# ScreenBoard.net
KiCad netlist of a schematic drawn in Altium Designer
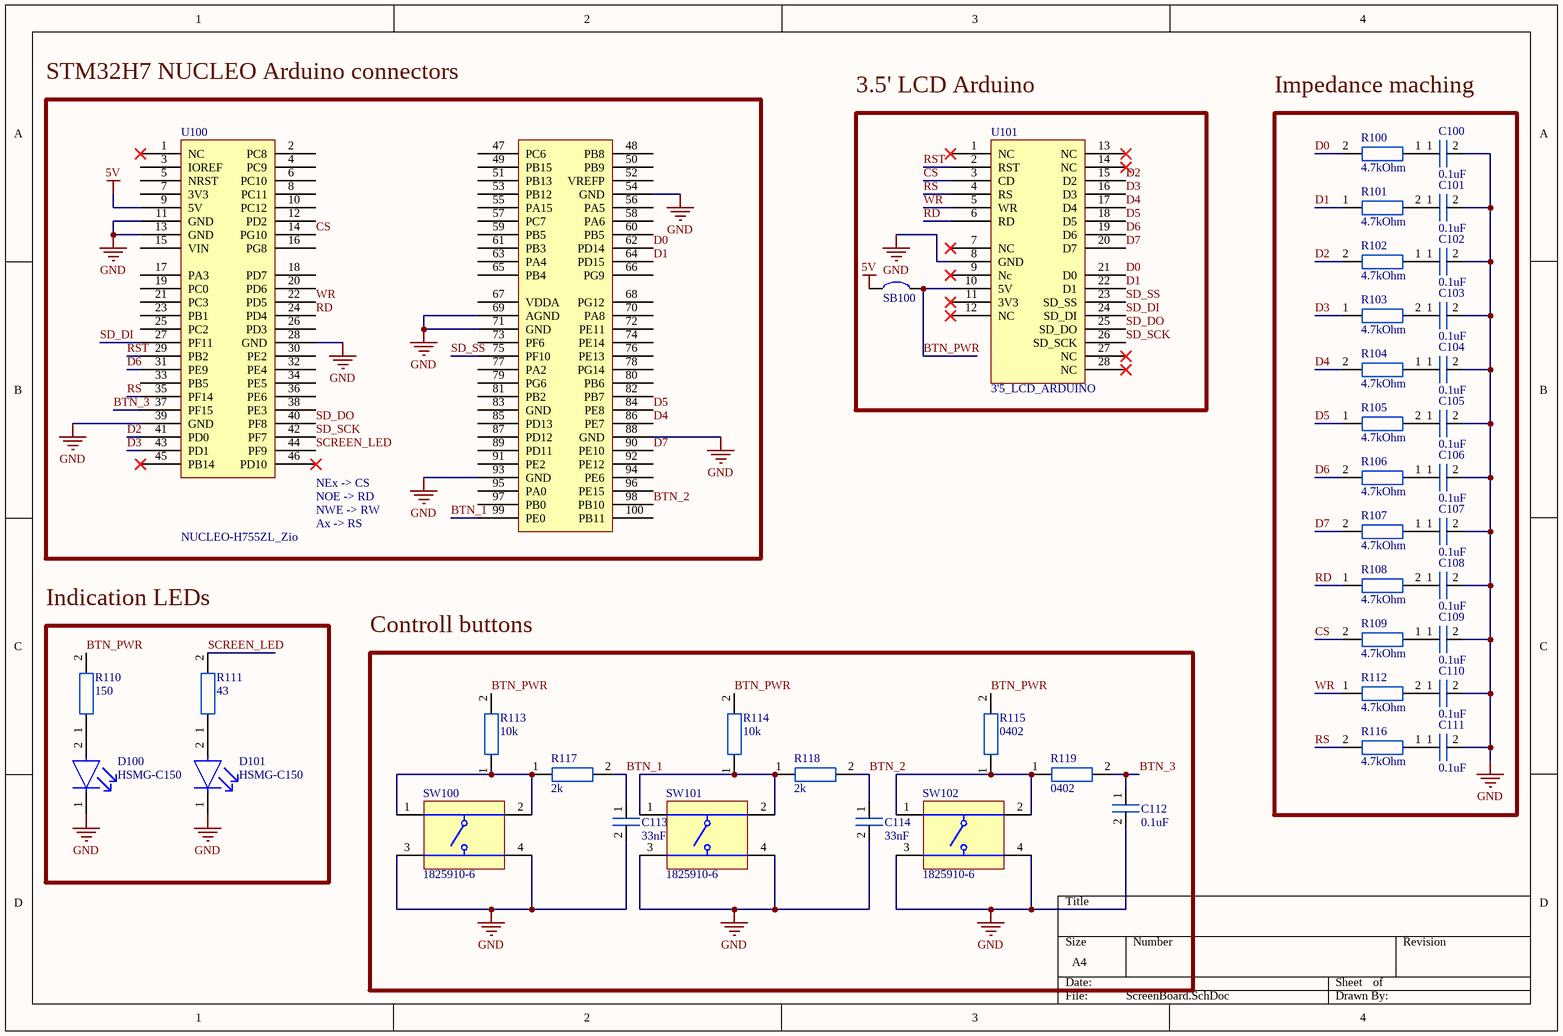
[diagram p0: ScreenBoard.SchDoc]

(export (version "E")
  (design (tool "Eeschema 10.0.6"))
  (components
    (comp (ref "C100")
      (value "0.1uF")
      (footprint "0402_footprint")
      (description "0402 capacitor")
      (libsource (lib "Schlib1") (part "Capacitor_0402"))
    )
    (comp (ref "C101")
      (value "0.1uF")
      (footprint "0402_footprint")
      (description "0402 capacitor")
      (libsource (lib "Schlib1") (part "Capacitor_0402"))
    )
    (comp (ref "C102")
      (value "0.1uF")
      (footprint "0402_footprint")
      (description "0402 capacitor")
      (libsource (lib "Schlib1") (part "Capacitor_0402"))
    )
    (comp (ref "C103")
      (value "0.1uF")
      (footprint "0402_footprint")
      (description "0402 capacitor")
      (libsource (lib "Schlib1") (part "Capacitor_0402"))
    )
    (comp (ref "C104")
      (value "0.1uF")
      (footprint "0402_footprint")
      (description "0402 capacitor")
      (libsource (lib "Schlib1") (part "Capacitor_0402"))
    )
    (comp (ref "C105")
      (value "0.1uF")
      (footprint "0402_footprint")
      (description "0402 capacitor")
      (libsource (lib "Schlib1") (part "Capacitor_0402"))
    )
    (comp (ref "C106")
      (value "0.1uF")
      (footprint "0402_footprint")
      (description "0402 capacitor")
      (libsource (lib "Schlib1") (part "Capacitor_0402"))
    )
    (comp (ref "C107")
      (value "0.1uF")
      (footprint "0402_footprint")
      (description "0402 capacitor")
      (libsource (lib "Schlib1") (part "Capacitor_0402"))
    )
    (comp (ref "C108")
      (value "0.1uF")
      (footprint "0402_footprint")
      (description "0402 capacitor")
      (libsource (lib "Schlib1") (part "Capacitor_0402"))
    )
    (comp (ref "C109")
      (value "0.1uF")
      (footprint "0402_footprint")
      (description "0402 capacitor")
      (libsource (lib "Schlib1") (part "Capacitor_0402"))
    )
    (comp (ref "C110")
      (value "0.1uF")
      (footprint "0402_footprint")
      (description "0402 capacitor")
      (libsource (lib "Schlib1") (part "Capacitor_0402"))
    )
    (comp (ref "C111")
      (value "0.1uF")
      (footprint "0402_footprint")
      (description "0402 capacitor")
      (libsource (lib "Schlib1") (part "Capacitor_0402"))
    )
    (comp (ref "C112")
      (value "0.1uF")
      (footprint "0402_footprint")
      (description "0402 capacitor")
      (libsource (lib "Schlib1") (part "Capacitor_0402"))
    )
    (comp (ref "C113")
      (value "33nF")
      (footprint "0402_footprint")
      (description "0402 capacitor")
      (libsource (lib "Schlib1") (part "Capacitor_0402"))
    )
    (comp (ref "C114")
      (value "33nF")
      (footprint "0402_footprint")
      (description "0402 capacitor")
      (libsource (lib "Schlib1") (part "Capacitor_0402"))
    )
    (comp (ref "D100")
      (value "HSMG-C150")
      (footprint "FP-HSMG-C150-MFG")
      (description "LED GREEN DIFFUSED 1206 SMD")
      (fields
        (field (name "MANUFACTURER") "Broadcom")
        (field (name "OCTOPART") "https://octopart.com/hsmg-c150-broadcom-71131304")
      )
      (libsource (lib "Altium Content Vault") (part "8706943c75ba83719d021d2fdc84c58"))
    )
    (comp (ref "D101")
      (value "HSMG-C150")
      (footprint "FP-HSMG-C150-MFG")
      (description "LED GREEN DIFFUSED 1206 SMD")
      (fields
        (field (name "MANUFACTURER") "Broadcom")
        (field (name "OCTOPART") "https://octopart.com/hsmg-c150-broadcom-71131304")
      )
      (libsource (lib "Altium Content Vault") (part "8706943c75ba83719d021d2fdc84c58"))
    )
    (comp (ref "R100")
      (value "4.7kOhm")
      (footprint "0402_footprint")
      (description "0402 resistor")
      (libsource (lib "Schlib1") (part "Resistor_0402"))
    )
    (comp (ref "R101")
      (value "4.7kOhm")
      (footprint "0402_footprint")
      (description "0402 resistor")
      (libsource (lib "Schlib1") (part "Resistor_0402"))
    )
    (comp (ref "R102")
      (value "4.7kOhm")
      (footprint "0402_footprint")
      (description "0402 resistor")
      (libsource (lib "Schlib1") (part "Resistor_0402"))
    )
    (comp (ref "R103")
      (value "4.7kOhm")
      (footprint "0402_footprint")
      (description "0402 resistor")
      (libsource (lib "Schlib1") (part "Resistor_0402"))
    )
    (comp (ref "R104")
      (value "4.7kOhm")
      (footprint "0402_footprint")
      (description "0402 resistor")
      (libsource (lib "Schlib1") (part "Resistor_0402"))
    )
    (comp (ref "R105")
      (value "4.7kOhm")
      (footprint "0402_footprint")
      (description "0402 resistor")
      (libsource (lib "Schlib1") (part "Resistor_0402"))
    )
    (comp (ref "R106")
      (value "4.7kOhm")
      (footprint "0402_footprint")
      (description "0402 resistor")
      (libsource (lib "Schlib1") (part "Resistor_0402"))
    )
    (comp (ref "R107")
      (value "4.7kOhm")
      (footprint "0402_footprint")
      (description "0402 resistor")
      (libsource (lib "Schlib1") (part "Resistor_0402"))
    )
    (comp (ref "R108")
      (value "4.7kOhm")
      (footprint "0402_footprint")
      (description "0402 resistor")
      (libsource (lib "Schlib1") (part "Resistor_0402"))
    )
    (comp (ref "R109")
      (value "4.7kOhm")
      (footprint "0402_footprint")
      (description "0402 resistor")
      (libsource (lib "Schlib1") (part "Resistor_0402"))
    )
    (comp (ref "R110")
      (value "150")
      (footprint "0402_footprint")
      (description "0402 resistor")
      (libsource (lib "Schlib1") (part "Resistor_0402"))
    )
    (comp (ref "R111")
      (value "43")
      (footprint "0402_footprint")
      (description "0402 resistor")
      (libsource (lib "Schlib1") (part "Resistor_0402"))
    )
    (comp (ref "R112")
      (value "4.7kOhm")
      (footprint "0402_footprint")
      (description "0402 resistor")
      (libsource (lib "Schlib1") (part "Resistor_0402"))
    )
    (comp (ref "R113")
      (value "10k")
      (footprint "0402_footprint")
      (description "0402 resistor")
      (libsource (lib "Schlib1") (part "Resistor_0402"))
    )
    (comp (ref "R114")
      (value "10k")
      (footprint "0402_footprint")
      (description "0402 resistor")
      (libsource (lib "Schlib1") (part "Resistor_0402"))
    )
    (comp (ref "R115")
      (value "0402")
      (footprint "0402_footprint")
      (description "0402 resistor")
      (libsource (lib "Schlib1") (part "Resistor_0402"))
    )
    (comp (ref "R116")
      (value "4.7kOhm")
      (footprint "0402_footprint")
      (description "0402 resistor")
      (libsource (lib "Schlib1") (part "Resistor_0402"))
    )
    (comp (ref "R117")
      (value "2k")
      (footprint "0402_footprint")
      (description "0402 resistor")
      (libsource (lib "Schlib1") (part "Resistor_0402"))
    )
    (comp (ref "R118")
      (value "2k")
      (footprint "0402_footprint")
      (description "0402 resistor")
      (libsource (lib "Schlib1") (part "Resistor_0402"))
    )
    (comp (ref "R119")
      (value "0402")
      (footprint "0402_footprint")
      (description "0402 resistor")
      (libsource (lib "Schlib1") (part "Resistor_0402"))
    )
    (comp (ref "SB100")
      (value "Solder_bridge")
      (footprint "SOLDER_BRIDGE")
      (libsource (lib "Schlib1") (part "Solder_bridge"))
    )
    (comp (ref "SW100")
      (value "1825910-6")
      (footprint "TECO-1825910-6_V")
      (description "Tact Switch, SPST-NO, 0.05 A, -35 to 85 degC, 4-Pin THD, RoHS, Bulk")
      (fields (field (name "MANUFACTURER") "TE Connectivity"))
      (libsource (lib "Altium Content Vault") (part "SW-SPST-4_A"))
    )
    (comp (ref "SW101")
      (value "1825910-6")
      (footprint "TECO-1825910-6_V")
      (description "Tact Switch, SPST-NO, 0.05 A, -35 to 85 degC, 4-Pin THD, RoHS, Bulk")
      (fields (field (name "MANUFACTURER") "TE Connectivity"))
      (libsource (lib "Altium Content Vault") (part "SW-SPST-4_A"))
    )
    (comp (ref "SW102")
      (value "1825910-6")
      (footprint "TECO-1825910-6_V")
      (description "Tact Switch, SPST-NO, 0.05 A, -35 to 85 degC, 4-Pin THD, RoHS, Bulk")
      (fields (field (name "MANUFACTURER") "TE Connectivity"))
      (libsource (lib "Altium Content Vault") (part "SW-SPST-4_A"))
    )
    (comp (ref "U100")
      (value "NUCLEO-H755ZL_Zio")
      (footprint "H7/H5_NUCLEO_Zio")
      (libsource (lib "Schlib1") (part "NUCLEO-H755ZL_Zio"))
    )
    (comp (ref "U101")
      (value "3'5_LCD_ARDUINO")
      (footprint "3'5_LCD_ARDUINO")
      (libsource (lib "Schlib1") (part "3'5_LCD_ARDUINO"))
    )
  )
  (nets
    (net (code "1") (name "/BTN_1") (class "Default")
      (node (ref "C113") (pin "1") (pinfunction "1_1") (pintype "passive"))
      (node (ref "R117") (pin "2") (pinfunction "2_2") (pintype "passive"))
      (node (ref "U100") (pin "99") (pinfunction "PE0_99") (pintype "passive"))
    )
    (net (code "2") (name "/BTN_2") (class "Default")
      (node (ref "C114") (pin "1") (pinfunction "1_1") (pintype "passive"))
      (node (ref "R118") (pin "2") (pinfunction "2_2") (pintype "passive"))
      (node (ref "U100") (pin "98") (pinfunction "PB10_98") (pintype "passive"))
    )
    (net (code "3") (name "/BTN_3") (class "Default")
      (node (ref "C112") (pin "1") (pinfunction "1_1") (pintype "passive"))
      (node (ref "R119") (pin "2") (pinfunction "2_2") (pintype "passive"))
      (node (ref "U100") (pin "37") (pinfunction "PF15_37") (pintype "passive"))
    )
    (net (code "4") (name "/BTN_PWR") (class "Default")
      (node (ref "R110") (pin "2") (pinfunction "2_2") (pintype "passive"))
      (node (ref "R113") (pin "2") (pinfunction "2_2") (pintype "passive"))
      (node (ref "R114") (pin "2") (pinfunction "2_2") (pintype "passive"))
      (node (ref "R115") (pin "2") (pinfunction "2_2") (pintype "passive"))
      (node (ref "SB100") (pin "2") (pinfunction "2_2") (pintype "passive"))
      (node (ref "U101") (pin "10") (pinfunction "5V_10") (pintype "passive"))
    )
    (net (code "5") (name "/CS") (class "Default")
      (node (ref "R109") (pin "2") (pinfunction "2_2") (pintype "passive"))
      (node (ref "U100") (pin "14") (pinfunction "PG10_14") (pintype "passive"))
      (node (ref "U101") (pin "3") (pinfunction "CD_3") (pintype "passive"))
    )
    (net (code "6") (name "/D0") (class "Default")
      (node (ref "R100") (pin "2") (pinfunction "2_2") (pintype "passive"))
      (node (ref "U100") (pin "62") (pinfunction "PD14_62") (pintype "passive"))
      (node (ref "U101") (pin "21") (pinfunction "D0_21") (pintype "passive"))
    )
    (net (code "7") (name "/D1") (class "Default")
      (node (ref "R101") (pin "1") (pinfunction "1_1") (pintype "passive"))
      (node (ref "U100") (pin "64") (pinfunction "PD15_64") (pintype "passive"))
      (node (ref "U101") (pin "22") (pinfunction "D1_22") (pintype "passive"))
    )
    (net (code "8") (name "/D2") (class "Default")
      (node (ref "R102") (pin "2") (pinfunction "2_2") (pintype "passive"))
      (node (ref "U100") (pin "41") (pinfunction "PD0_41") (pintype "passive"))
      (node (ref "U101") (pin "15") (pinfunction "D2_15") (pintype "passive"))
    )
    (net (code "9") (name "/D3") (class "Default")
      (node (ref "R103") (pin "1") (pinfunction "1_1") (pintype "passive"))
      (node (ref "U100") (pin "43") (pinfunction "PD1_43") (pintype "passive"))
      (node (ref "U101") (pin "16") (pinfunction "D3_16") (pintype "passive"))
    )
    (net (code "10") (name "/D4") (class "Default")
      (node (ref "R104") (pin "2") (pinfunction "2_2") (pintype "passive"))
      (node (ref "U100") (pin "86") (pinfunction "PE7_86") (pintype "passive"))
      (node (ref "U101") (pin "17") (pinfunction "D4_17") (pintype "passive"))
    )
    (net (code "11") (name "/D5") (class "Default")
      (node (ref "R105") (pin "1") (pinfunction "1_1") (pintype "passive"))
      (node (ref "U100") (pin "84") (pinfunction "PE8_84") (pintype "passive"))
      (node (ref "U101") (pin "18") (pinfunction "D5_18") (pintype "passive"))
    )
    (net (code "12") (name "/D6") (class "Default")
      (node (ref "R106") (pin "2") (pinfunction "2_2") (pintype "passive"))
      (node (ref "U100") (pin "31") (pinfunction "PE9_31") (pintype "passive"))
      (node (ref "U101") (pin "19") (pinfunction "D6_19") (pintype "passive"))
    )
    (net (code "13") (name "/D7") (class "Default")
      (node (ref "R107") (pin "2") (pinfunction "2_2") (pintype "passive"))
      (node (ref "U100") (pin "90") (pinfunction "PE10_90") (pintype "passive"))
      (node (ref "U101") (pin "20") (pinfunction "D7_20") (pintype "passive"))
    )
    (net (code "14") (name "/RD") (class "Default")
      (node (ref "R108") (pin "1") (pinfunction "1_1") (pintype "passive"))
      (node (ref "U100") (pin "24") (pinfunction "PD4_24") (pintype "passive"))
      (node (ref "U101") (pin "6") (pinfunction "RD_6") (pintype "passive"))
    )
    (net (code "15") (name "/RS") (class "Default")
      (node (ref "R116") (pin "2") (pinfunction "2_2") (pintype "passive"))
      (node (ref "U100") (pin "35") (pinfunction "PF14_35") (pintype "passive"))
      (node (ref "U101") (pin "4") (pinfunction "RS_4") (pintype "passive"))
    )
    (net (code "16") (name "/RST") (class "Default")
      (node (ref "U100") (pin "29") (pinfunction "PB2_29") (pintype "passive"))
      (node (ref "U101") (pin "2") (pinfunction "RST_2") (pintype "passive"))
    )
    (net (code "17") (name "/SCREEN_LED") (class "Default")
      (node (ref "R111") (pin "2") (pinfunction "2_2") (pintype "passive"))
      (node (ref "U100") (pin "44") (pinfunction "PF9_44") (pintype "passive"))
    )
    (net (code "18") (name "/SD_DI") (class "Default")
      (node (ref "U100") (pin "27") (pinfunction "PF11_27") (pintype "passive"))
      (node (ref "U101") (pin "24") (pinfunction "SD_DI_24") (pintype "passive"))
    )
    (net (code "19") (name "/SD_DO") (class "Default")
      (node (ref "U100") (pin "40") (pinfunction "PF8_40") (pintype "passive"))
      (node (ref "U101") (pin "25") (pinfunction "SD_DO_25") (pintype "passive"))
    )
    (net (code "20") (name "/SD_SCK") (class "Default")
      (node (ref "U100") (pin "42") (pinfunction "PF7_42") (pintype "passive"))
      (node (ref "U101") (pin "26") (pinfunction "SD_SCK_26") (pintype "passive"))
    )
    (net (code "21") (name "/SD_SS") (class "Default")
      (node (ref "U100") (pin "75") (pinfunction "PF10_75") (pintype "passive"))
      (node (ref "U101") (pin "23") (pinfunction "SD_SS_23") (pintype "passive"))
    )
    (net (code "22") (name "/WR") (class "Default")
      (node (ref "R112") (pin "1") (pinfunction "1_1") (pintype "passive"))
      (node (ref "U100") (pin "22") (pinfunction "PD5_22") (pintype "passive"))
      (node (ref "U101") (pin "5") (pinfunction "WR_5") (pintype "passive"))
    )
    (net (code "23") (name "5V") (class "Default")
      (node (ref "SB100") (pin "1") (pinfunction "1_1") (pintype "passive"))
      (node (ref "U100") (pin "9") (pinfunction "5V_9") (pintype "passive"))
    )
    (net (code "24") (name "GND") (class "Default")
      (node (ref "C100") (pin "2") (pinfunction "2_2") (pintype "passive"))
      (node (ref "C101") (pin "2") (pinfunction "2_2") (pintype "passive"))
      (node (ref "C102") (pin "2") (pinfunction "2_2") (pintype "passive"))
      (node (ref "C103") (pin "2") (pinfunction "2_2") (pintype "passive"))
      (node (ref "C104") (pin "2") (pinfunction "2_2") (pintype "passive"))
      (node (ref "C105") (pin "2") (pinfunction "2_2") (pintype "passive"))
      (node (ref "C106") (pin "2") (pinfunction "2_2") (pintype "passive"))
      (node (ref "C107") (pin "2") (pinfunction "2_2") (pintype "passive"))
      (node (ref "C108") (pin "2") (pinfunction "2_2") (pintype "passive"))
      (node (ref "C109") (pin "2") (pinfunction "2_2") (pintype "passive"))
      (node (ref "C110") (pin "2") (pinfunction "2_2") (pintype "passive"))
      (node (ref "C111") (pin "2") (pinfunction "2_2") (pintype "passive"))
      (node (ref "C112") (pin "2") (pinfunction "2_2") (pintype "passive"))
      (node (ref "C113") (pin "2") (pinfunction "2_2") (pintype "passive"))
      (node (ref "C114") (pin "2") (pinfunction "2_2") (pintype "passive"))
      (node (ref "D100") (pin "1") (pinfunction "C_1") (pintype "passive"))
      (node (ref "D101") (pin "1") (pinfunction "C_1") (pintype "passive"))
      (node (ref "SW100") (pin "3") (pinfunction "3_3") (pintype "passive"))
      (node (ref "SW100") (pin "4") (pinfunction "4_4") (pintype "passive"))
      (node (ref "SW101") (pin "3") (pinfunction "3_3") (pintype "passive"))
      (node (ref "SW101") (pin "4") (pinfunction "4_4") (pintype "passive"))
      (node (ref "SW102") (pin "3") (pinfunction "3_3") (pintype "passive"))
      (node (ref "SW102") (pin "4") (pinfunction "4_4") (pintype "passive"))
      (node (ref "U100") (pin "11") (pinfunction "GND_11") (pintype "passive"))
      (node (ref "U100") (pin "13") (pinfunction "GND_13") (pintype "passive"))
      (node (ref "U100") (pin "28") (pinfunction "GND_28") (pintype "passive"))
      (node (ref "U100") (pin "39") (pinfunction "GND_39") (pintype "passive"))
      (node (ref "U100") (pin "54") (pinfunction "GND_54") (pintype "passive"))
      (node (ref "U100") (pin "69") (pinfunction "AGND_69") (pintype "passive"))
      (node (ref "U100") (pin "71") (pinfunction "GND_71") (pintype "passive"))
      (node (ref "U100") (pin "88") (pinfunction "GND_88") (pintype "passive"))
      (node (ref "U100") (pin "93") (pinfunction "GND_93") (pintype "passive"))
      (node (ref "U101") (pin "8") (pinfunction "GND_8") (pintype "passive"))
    )
    (net (code "25") (name "Net-(C100-Pad1)") (class "Default")
      (node (ref "C100") (pin "1") (pinfunction "1_1") (pintype "passive"))
      (node (ref "R100") (pin "1") (pinfunction "1_1") (pintype "passive"))
    )
    (net (code "26") (name "Net-(C101-Pad1)") (class "Default")
      (node (ref "C101") (pin "1") (pinfunction "1_1") (pintype "passive"))
      (node (ref "R101") (pin "2") (pinfunction "2_2") (pintype "passive"))
    )
    (net (code "27") (name "Net-(C102-Pad1)") (class "Default")
      (node (ref "C102") (pin "1") (pinfunction "1_1") (pintype "passive"))
      (node (ref "R102") (pin "1") (pinfunction "1_1") (pintype "passive"))
    )
    (net (code "28") (name "Net-(C103-Pad1)") (class "Default")
      (node (ref "C103") (pin "1") (pinfunction "1_1") (pintype "passive"))
      (node (ref "R103") (pin "2") (pinfunction "2_2") (pintype "passive"))
    )
    (net (code "29") (name "Net-(C104-Pad1)") (class "Default")
      (node (ref "C104") (pin "1") (pinfunction "1_1") (pintype "passive"))
      (node (ref "R104") (pin "1") (pinfunction "1_1") (pintype "passive"))
    )
    (net (code "30") (name "Net-(C105-Pad1)") (class "Default")
      (node (ref "C105") (pin "1") (pinfunction "1_1") (pintype "passive"))
      (node (ref "R105") (pin "2") (pinfunction "2_2") (pintype "passive"))
    )
    (net (code "31") (name "Net-(C106-Pad1)") (class "Default")
      (node (ref "C106") (pin "1") (pinfunction "1_1") (pintype "passive"))
      (node (ref "R106") (pin "1") (pinfunction "1_1") (pintype "passive"))
    )
    (net (code "32") (name "Net-(C107-Pad1)") (class "Default")
      (node (ref "C107") (pin "1") (pinfunction "1_1") (pintype "passive"))
      (node (ref "R107") (pin "1") (pinfunction "1_1") (pintype "passive"))
    )
    (net (code "33") (name "Net-(C108-Pad1)") (class "Default")
      (node (ref "C108") (pin "1") (pinfunction "1_1") (pintype "passive"))
      (node (ref "R108") (pin "2") (pinfunction "2_2") (pintype "passive"))
    )
    (net (code "34") (name "Net-(C109-Pad1)") (class "Default")
      (node (ref "C109") (pin "1") (pinfunction "1_1") (pintype "passive"))
      (node (ref "R109") (pin "1") (pinfunction "1_1") (pintype "passive"))
    )
    (net (code "35") (name "Net-(C110-Pad1)") (class "Default")
      (node (ref "C110") (pin "1") (pinfunction "1_1") (pintype "passive"))
      (node (ref "R112") (pin "2") (pinfunction "2_2") (pintype "passive"))
    )
    (net (code "36") (name "Net-(C111-Pad1)") (class "Default")
      (node (ref "C111") (pin "1") (pinfunction "1_1") (pintype "passive"))
      (node (ref "R116") (pin "1") (pinfunction "1_1") (pintype "passive"))
    )
    (net (code "37") (name "Net-(D100-A)") (class "Default")
      (node (ref "D100") (pin "2") (pinfunction "A_2") (pintype "passive"))
      (node (ref "R110") (pin "1") (pinfunction "1_1") (pintype "passive"))
    )
    (net (code "38") (name "Net-(D101-A)") (class "Default")
      (node (ref "D101") (pin "2") (pinfunction "A_2") (pintype "passive"))
      (node (ref "R111") (pin "1") (pinfunction "1_1") (pintype "passive"))
    )
    (net (code "39") (name "Net-(R113-Pad1)") (class "Default")
      (node (ref "R113") (pin "1") (pinfunction "1_1") (pintype "passive"))
      (node (ref "R117") (pin "1") (pinfunction "1_1") (pintype "passive"))
      (node (ref "SW100") (pin "1") (pinfunction "1_1") (pintype "passive"))
      (node (ref "SW100") (pin "2") (pinfunction "2_2") (pintype "passive"))
    )
    (net (code "40") (name "Net-(R114-Pad1)") (class "Default")
      (node (ref "R114") (pin "1") (pinfunction "1_1") (pintype "passive"))
      (node (ref "R118") (pin "1") (pinfunction "1_1") (pintype "passive"))
      (node (ref "SW101") (pin "1") (pinfunction "1_1") (pintype "passive"))
      (node (ref "SW101") (pin "2") (pinfunction "2_2") (pintype "passive"))
    )
    (net (code "41") (name "Net-(R115-Pad1)") (class "Default")
      (node (ref "R115") (pin "1") (pinfunction "1_1") (pintype "passive"))
      (node (ref "R119") (pin "1") (pinfunction "1_1") (pintype "passive"))
      (node (ref "SW102") (pin "1") (pinfunction "1_1") (pintype "passive"))
      (node (ref "SW102") (pin "2") (pinfunction "2_2") (pintype "passive"))
    )
    (net (code "42") (name "unconnected-(U100-3V3-Pad7)") (class "Default")
      (node (ref "U100") (pin "7") (pinfunction "3V3_7") (pintype "passive"))
    )
    (net (code "43") (name "unconnected-(U100-GND-Pad83)") (class "Default")
      (node (ref "U100") (pin "83") (pinfunction "GND_83") (pintype "passive"))
    )
    (net (code "44") (name "unconnected-(U100-IOREF-Pad3)") (class "Default")
      (node (ref "U100") (pin "3") (pinfunction "IOREF_3") (pintype "passive"))
    )
    (net (code "45") (name "unconnected-(U100-NC-Pad1)") (class "Default")
      (node (ref "U100") (pin "1") (pinfunction "NC_1") (pintype "passive+no_connect"))
    )
    (net (code "46") (name "unconnected-(U100-NRST-Pad5)") (class "Default")
      (node (ref "U100") (pin "5") (pinfunction "NRST_5") (pintype "passive"))
    )
    (net (code "47") (name "unconnected-(U100-PA0-Pad95)") (class "Default")
      (node (ref "U100") (pin "95") (pinfunction "PA0_95") (pintype "passive"))
    )
    (net (code "48") (name "unconnected-(U100-PA2-Pad77)") (class "Default")
      (node (ref "U100") (pin "77") (pinfunction "PA2_77") (pintype "passive"))
    )
    (net (code "49") (name "unconnected-(U100-PA3-Pad17)") (class "Default")
      (node (ref "U100") (pin "17") (pinfunction "PA3_17") (pintype "passive"))
    )
    (net (code "50") (name "unconnected-(U100-PA4-Pad63)") (class "Default")
      (node (ref "U100") (pin "63") (pinfunction "PA4_63") (pintype "passive"))
    )
    (net (code "51") (name "unconnected-(U100-PA5-Pad56)") (class "Default")
      (node (ref "U100") (pin "56") (pinfunction "PA5_56") (pintype "passive"))
    )
    (net (code "52") (name "unconnected-(U100-PA6-Pad58)") (class "Default")
      (node (ref "U100") (pin "58") (pinfunction "PA6_58") (pintype "passive"))
    )
    (net (code "53") (name "unconnected-(U100-PA8-Pad70)") (class "Default")
      (node (ref "U100") (pin "70") (pinfunction "PA8_70") (pintype "passive"))
    )
    (net (code "54") (name "unconnected-(U100-PA15-Pad55)") (class "Default")
      (node (ref "U100") (pin "55") (pinfunction "PA15_55") (pintype "passive"))
    )
    (net (code "55") (name "unconnected-(U100-PB0-Pad97)") (class "Default")
      (node (ref "U100") (pin "97") (pinfunction "PB0_97") (pintype "passive"))
    )
    (net (code "56") (name "unconnected-(U100-PB1-Pad23)") (class "Default")
      (node (ref "U100") (pin "23") (pinfunction "PB1_23") (pintype "passive"))
    )
    (net (code "57") (name "unconnected-(U100-PB2-Pad81)") (class "Default")
      (node (ref "U100") (pin "81") (pinfunction "PB2_81") (pintype "passive"))
    )
    (net (code "58") (name "unconnected-(U100-PB3-Pad61)") (class "Default")
      (node (ref "U100") (pin "61") (pinfunction "PB3_61") (pintype "passive"))
    )
    (net (code "59") (name "unconnected-(U100-PB4-Pad65)") (class "Default")
      (node (ref "U100") (pin "65") (pinfunction "PB4_65") (pintype "passive"))
    )
    (net (code "60") (name "unconnected-(U100-PB5-Pad33)") (class "Default")
      (node (ref "U100") (pin "33") (pinfunction "PB5_33") (pintype "passive"))
    )
    (net (code "61") (name "unconnected-(U100-PB5-Pad59)") (class "Default")
      (node (ref "U100") (pin "59") (pinfunction "PB5_59") (pintype "passive"))
    )
    (net (code "62") (name "unconnected-(U100-PB5-Pad60)") (class "Default")
      (node (ref "U100") (pin "60") (pinfunction "PB5_60") (pintype "passive"))
    )
    (net (code "63") (name "unconnected-(U100-PB6-Pad80)") (class "Default")
      (node (ref "U100") (pin "80") (pinfunction "PB6_80") (pintype "passive"))
    )
    (net (code "64") (name "unconnected-(U100-PB7-Pad82)") (class "Default")
      (node (ref "U100") (pin "82") (pinfunction "PB7_82") (pintype "passive"))
    )
    (net (code "65") (name "unconnected-(U100-PB8-Pad48)") (class "Default")
      (node (ref "U100") (pin "48") (pinfunction "PB8_48") (pintype "passive"))
    )
    (net (code "66") (name "unconnected-(U100-PB9-Pad50)") (class "Default")
      (node (ref "U100") (pin "50") (pinfunction "PB9_50") (pintype "passive"))
    )
    (net (code "67") (name "unconnected-(U100-PB11-Pad100)") (class "Default")
      (node (ref "U100") (pin "100") (pinfunction "PB11_100") (pintype "passive"))
    )
    (net (code "68") (name "unconnected-(U100-PB12-Pad53)") (class "Default")
      (node (ref "U100") (pin "53") (pinfunction "PB12_53") (pintype "passive"))
    )
    (net (code "69") (name "unconnected-(U100-PB13-Pad51)") (class "Default")
      (node (ref "U100") (pin "51") (pinfunction "PB13_51") (pintype "passive"))
    )
    (net (code "70") (name "unconnected-(U100-PB14-Pad45)") (class "Default")
      (node (ref "U100") (pin "45") (pinfunction "PB14_45") (pintype "passive+no_connect"))
    )
    (net (code "71") (name "unconnected-(U100-PB15-Pad49)") (class "Default")
      (node (ref "U100") (pin "49") (pinfunction "PB15_49") (pintype "passive"))
    )
    (net (code "72") (name "unconnected-(U100-PC0-Pad19)") (class "Default")
      (node (ref "U100") (pin "19") (pinfunction "PC0_19") (pintype "passive"))
    )
    (net (code "73") (name "unconnected-(U100-PC2-Pad25)") (class "Default")
      (node (ref "U100") (pin "25") (pinfunction "PC2_25") (pintype "passive"))
    )
    (net (code "74") (name "unconnected-(U100-PC3-Pad21)") (class "Default")
      (node (ref "U100") (pin "21") (pinfunction "PC3_21") (pintype "passive"))
    )
    (net (code "75") (name "unconnected-(U100-PC6-Pad47)") (class "Default")
      (node (ref "U100") (pin "47") (pinfunction "PC6_47") (pintype "passive"))
    )
    (net (code "76") (name "unconnected-(U100-PC7-Pad57)") (class "Default")
      (node (ref "U100") (pin "57") (pinfunction "PC7_57") (pintype "passive"))
    )
    (net (code "77") (name "unconnected-(U100-PC8-Pad2)") (class "Default")
      (node (ref "U100") (pin "2") (pinfunction "PC8_2") (pintype "passive"))
    )
    (net (code "78") (name "unconnected-(U100-PC9-Pad4)") (class "Default")
      (node (ref "U100") (pin "4") (pinfunction "PC9_4") (pintype "passive"))
    )
    (net (code "79") (name "unconnected-(U100-PC10-Pad6)") (class "Default")
      (node (ref "U100") (pin "6") (pinfunction "PC10_6") (pintype "passive"))
    )
    (net (code "80") (name "unconnected-(U100-PC11-Pad8)") (class "Default")
      (node (ref "U100") (pin "8") (pinfunction "PC11_8") (pintype "passive"))
    )
    (net (code "81") (name "unconnected-(U100-PC12-Pad10)") (class "Default")
      (node (ref "U100") (pin "10") (pinfunction "PC12_10") (pintype "passive"))
    )
    (net (code "82") (name "unconnected-(U100-PD2-Pad12)") (class "Default")
      (node (ref "U100") (pin "12") (pinfunction "PD2_12") (pintype "passive"))
    )
    (net (code "83") (name "unconnected-(U100-PD3-Pad26)") (class "Default")
      (node (ref "U100") (pin "26") (pinfunction "PD3_26") (pintype "passive"))
    )
    (net (code "84") (name "unconnected-(U100-PD6-Pad20)") (class "Default")
      (node (ref "U100") (pin "20") (pinfunction "PD6_20") (pintype "passive"))
    )
    (net (code "85") (name "unconnected-(U100-PD7-Pad18)") (class "Default")
      (node (ref "U100") (pin "18") (pinfunction "PD7_18") (pintype "passive"))
    )
    (net (code "86") (name "unconnected-(U100-PD10-Pad46)") (class "Default")
      (node (ref "U100") (pin "46") (pinfunction "PD10_46") (pintype "passive+no_connect"))
    )
    (net (code "87") (name "unconnected-(U100-PD11-Pad89)") (class "Default")
      (node (ref "U100") (pin "89") (pinfunction "PD11_89") (pintype "passive"))
    )
    (net (code "88") (name "unconnected-(U100-PD12-Pad87)") (class "Default")
      (node (ref "U100") (pin "87") (pinfunction "PD12_87") (pintype "passive"))
    )
    (net (code "89") (name "unconnected-(U100-PD13-Pad85)") (class "Default")
      (node (ref "U100") (pin "85") (pinfunction "PD13_85") (pintype "passive"))
    )
    (net (code "90") (name "unconnected-(U100-PE2-Pad30)") (class "Default")
      (node (ref "U100") (pin "30") (pinfunction "PE2_30") (pintype "passive"))
    )
    (net (code "91") (name "unconnected-(U100-PE2-Pad91)") (class "Default")
      (node (ref "U100") (pin "91") (pinfunction "PE2_91") (pintype "passive"))
    )
    (net (code "92") (name "unconnected-(U100-PE3-Pad38)") (class "Default")
      (node (ref "U100") (pin "38") (pinfunction "PE3_38") (pintype "passive"))
    )
    (net (code "93") (name "unconnected-(U100-PE4-Pad32)") (class "Default")
      (node (ref "U100") (pin "32") (pinfunction "PE4_32") (pintype "passive"))
    )
    (net (code "94") (name "unconnected-(U100-PE5-Pad34)") (class "Default")
      (node (ref "U100") (pin "34") (pinfunction "PE5_34") (pintype "passive"))
    )
    (net (code "95") (name "unconnected-(U100-PE6-Pad36)") (class "Default")
      (node (ref "U100") (pin "36") (pinfunction "PE6_36") (pintype "passive"))
    )
    (net (code "96") (name "unconnected-(U100-PE6-Pad94)") (class "Default")
      (node (ref "U100") (pin "94") (pinfunction "PE6_94") (pintype "passive"))
    )
    (net (code "97") (name "unconnected-(U100-PE11-Pad72)") (class "Default")
      (node (ref "U100") (pin "72") (pinfunction "PE11_72") (pintype "passive"))
    )
    (net (code "98") (name "unconnected-(U100-PE12-Pad92)") (class "Default")
      (node (ref "U100") (pin "92") (pinfunction "PE12_92") (pintype "passive"))
    )
    (net (code "99") (name "unconnected-(U100-PE13-Pad76)") (class "Default")
      (node (ref "U100") (pin "76") (pinfunction "PE13_76") (pintype "passive"))
    )
    (net (code "100") (name "unconnected-(U100-PE14-Pad74)") (class "Default")
      (node (ref "U100") (pin "74") (pinfunction "PE14_74") (pintype "passive"))
    )
    (net (code "101") (name "unconnected-(U100-PE15-Pad96)") (class "Default")
      (node (ref "U100") (pin "96") (pinfunction "PE15_96") (pintype "passive"))
    )
    (net (code "102") (name "unconnected-(U100-PF6-Pad73)") (class "Default")
      (node (ref "U100") (pin "73") (pinfunction "PF6_73") (pintype "passive"))
    )
    (net (code "103") (name "unconnected-(U100-PG6-Pad79)") (class "Default")
      (node (ref "U100") (pin "79") (pinfunction "PG6_79") (pintype "passive"))
    )
    (net (code "104") (name "unconnected-(U100-PG8-Pad16)") (class "Default")
      (node (ref "U100") (pin "16") (pinfunction "PG8_16") (pintype "passive"))
    )
    (net (code "105") (name "unconnected-(U100-PG9-Pad66)") (class "Default")
      (node (ref "U100") (pin "66") (pinfunction "PG9_66") (pintype "passive"))
    )
    (net (code "106") (name "unconnected-(U100-PG12-Pad68)") (class "Default")
      (node (ref "U100") (pin "68") (pinfunction "PG12_68") (pintype "passive"))
    )
    (net (code "107") (name "unconnected-(U100-PG14-Pad78)") (class "Default")
      (node (ref "U100") (pin "78") (pinfunction "PG14_78") (pintype "passive"))
    )
    (net (code "108") (name "unconnected-(U100-VDDA-Pad67)") (class "Default")
      (node (ref "U100") (pin "67") (pinfunction "VDDA_67") (pintype "passive"))
    )
    (net (code "109") (name "unconnected-(U100-VIN-Pad15)") (class "Default")
      (node (ref "U100") (pin "15") (pinfunction "VIN_15") (pintype "passive"))
    )
    (net (code "110") (name "unconnected-(U100-VREFP-Pad52)") (class "Default")
      (node (ref "U100") (pin "52") (pinfunction "VREFP_52") (pintype "passive"))
    )
    (net (code "111") (name "unconnected-(U101-3V3-Pad11)") (class "Default")
      (node (ref "U101") (pin "11") (pinfunction "3V3_11") (pintype "passive+no_connect"))
    )
    (net (code "112") (name "unconnected-(U101-NC-Pad1)") (class "Default")
      (node (ref "U101") (pin "1") (pinfunction "NC_1") (pintype "passive+no_connect"))
    )
    (net (code "113") (name "unconnected-(U101-NC-Pad7)") (class "Default")
      (node (ref "U101") (pin "7") (pinfunction "NC_7") (pintype "passive+no_connect"))
    )
    (net (code "114") (name "unconnected-(U101-NC-Pad12)") (class "Default")
      (node (ref "U101") (pin "12") (pinfunction "NC_12") (pintype "passive+no_connect"))
    )
    (net (code "115") (name "unconnected-(U101-NC-Pad13)") (class "Default")
      (node (ref "U101") (pin "13") (pinfunction "NC_13") (pintype "passive+no_connect"))
    )
    (net (code "116") (name "unconnected-(U101-NC-Pad14)") (class "Default")
      (node (ref "U101") (pin "14") (pinfunction "NC_14") (pintype "passive+no_connect"))
    )
    (net (code "117") (name "unconnected-(U101-NC-Pad27)") (class "Default")
      (node (ref "U101") (pin "27") (pinfunction "NC_27") (pintype "passive+no_connect"))
    )
    (net (code "118") (name "unconnected-(U101-NC-Pad28)") (class "Default")
      (node (ref "U101") (pin "28") (pinfunction "NC_28") (pintype "passive+no_connect"))
    )
    (net (code "119") (name "unconnected-(U101-Nc-Pad9)") (class "Default")
      (node (ref "U101") (pin "9") (pinfunction "Nc_9") (pintype "passive+no_connect"))
    )
  )
)
